# pmic_tps79933.net
KiCad netlist of a schematic drawn in Altium Designer
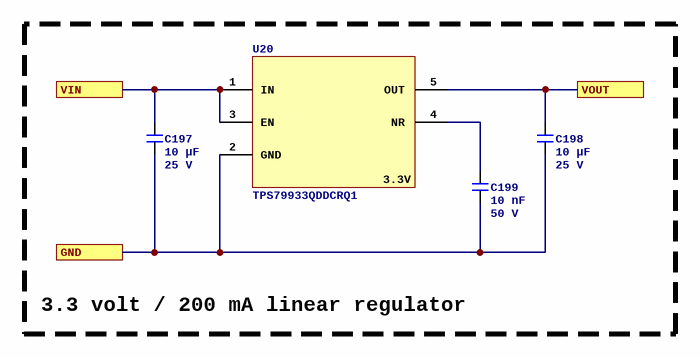
[diagram p0: pmic_tps79933.SchDoc]

(export (version "E")
  (design (tool "Eeschema 10.0.6"))
  (components
    (comp (ref "C197")
      (value "CL21B106KAYQNNE")
      (footprint "C0805")
      (fields
        (field (name "CAPACITANCE") "10 µF")
        (field (name "MANUFACTURER") "Samsung Electro-Mechanics")
        (field (name "VOLTAGE RATING") "25 V")
      )
      (libsource (lib "database") (part "__template_cap"))
    )
    (comp (ref "C198")
      (value "CL21B106KAYQNNE")
      (footprint "C0805")
      (fields
        (field (name "CAPACITANCE") "10 µF")
        (field (name "MANUFACTURER") "Samsung Electro-Mechanics")
        (field (name "VOLTAGE RATING") "25 V")
      )
      (libsource (lib "database") (part "__template_cap"))
    )
    (comp (ref "C199")
      (value "CL05B103KB5NNNC")
      (footprint "C0402")
      (fields
        (field (name "CAPACITANCE") "10 nF")
        (field (name "MANUFACTURER") "Samsung Electro-Mechanics")
        (field (name "VOLTAGE RATING") "50 V")
      )
      (libsource (lib "database") (part "__template_cap"))
    )
    (comp (ref "U20")
      (value "TPS79933QDDCRQ1")
      (footprint "5SOT23")
      (description "Fixed Positive LDO Regulator, 3.3V, 0.16V Dropout, BICMOS, PDSO5")
      (fields (field (name "MANUFACTURER") "Texas Instruments"))
      (libsource (lib "database") (part "TPS79933QDDCRQ1"))
    )
  )
  (nets
    (net (code "1") (name "/GND") (class "Default")
      (node (ref "C197") (pin "2") (pintype "passive"))
      (node (ref "C198") (pin "2") (pintype "passive"))
      (node (ref "C199") (pin "2") (pintype "passive"))
      (node (ref "U20") (pin "2") (pinfunction "GND_2") (pintype "passive"))
    )
    (net (code "2") (name "/VIN") (class "Default")
      (node (ref "C197") (pin "1") (pintype "passive"))
      (node (ref "U20") (pin "1") (pinfunction "IN_1") (pintype "passive"))
      (node (ref "U20") (pin "3") (pinfunction "EN_3") (pintype "passive"))
    )
    (net (code "3") (name "/VOUT") (class "Default")
      (node (ref "C198") (pin "1") (pintype "passive"))
      (node (ref "U20") (pin "5") (pinfunction "OUT_5") (pintype "passive"))
    )
    (net (code "4") (name "Net-(U20-NR)") (class "Default")
      (node (ref "C199") (pin "1") (pintype "passive"))
      (node (ref "U20") (pin "4") (pinfunction "NR_4") (pintype "passive"))
    )
  )
)
